# VA-Meter_Measure.net
KiCad netlist of a schematic drawn in EAGLE
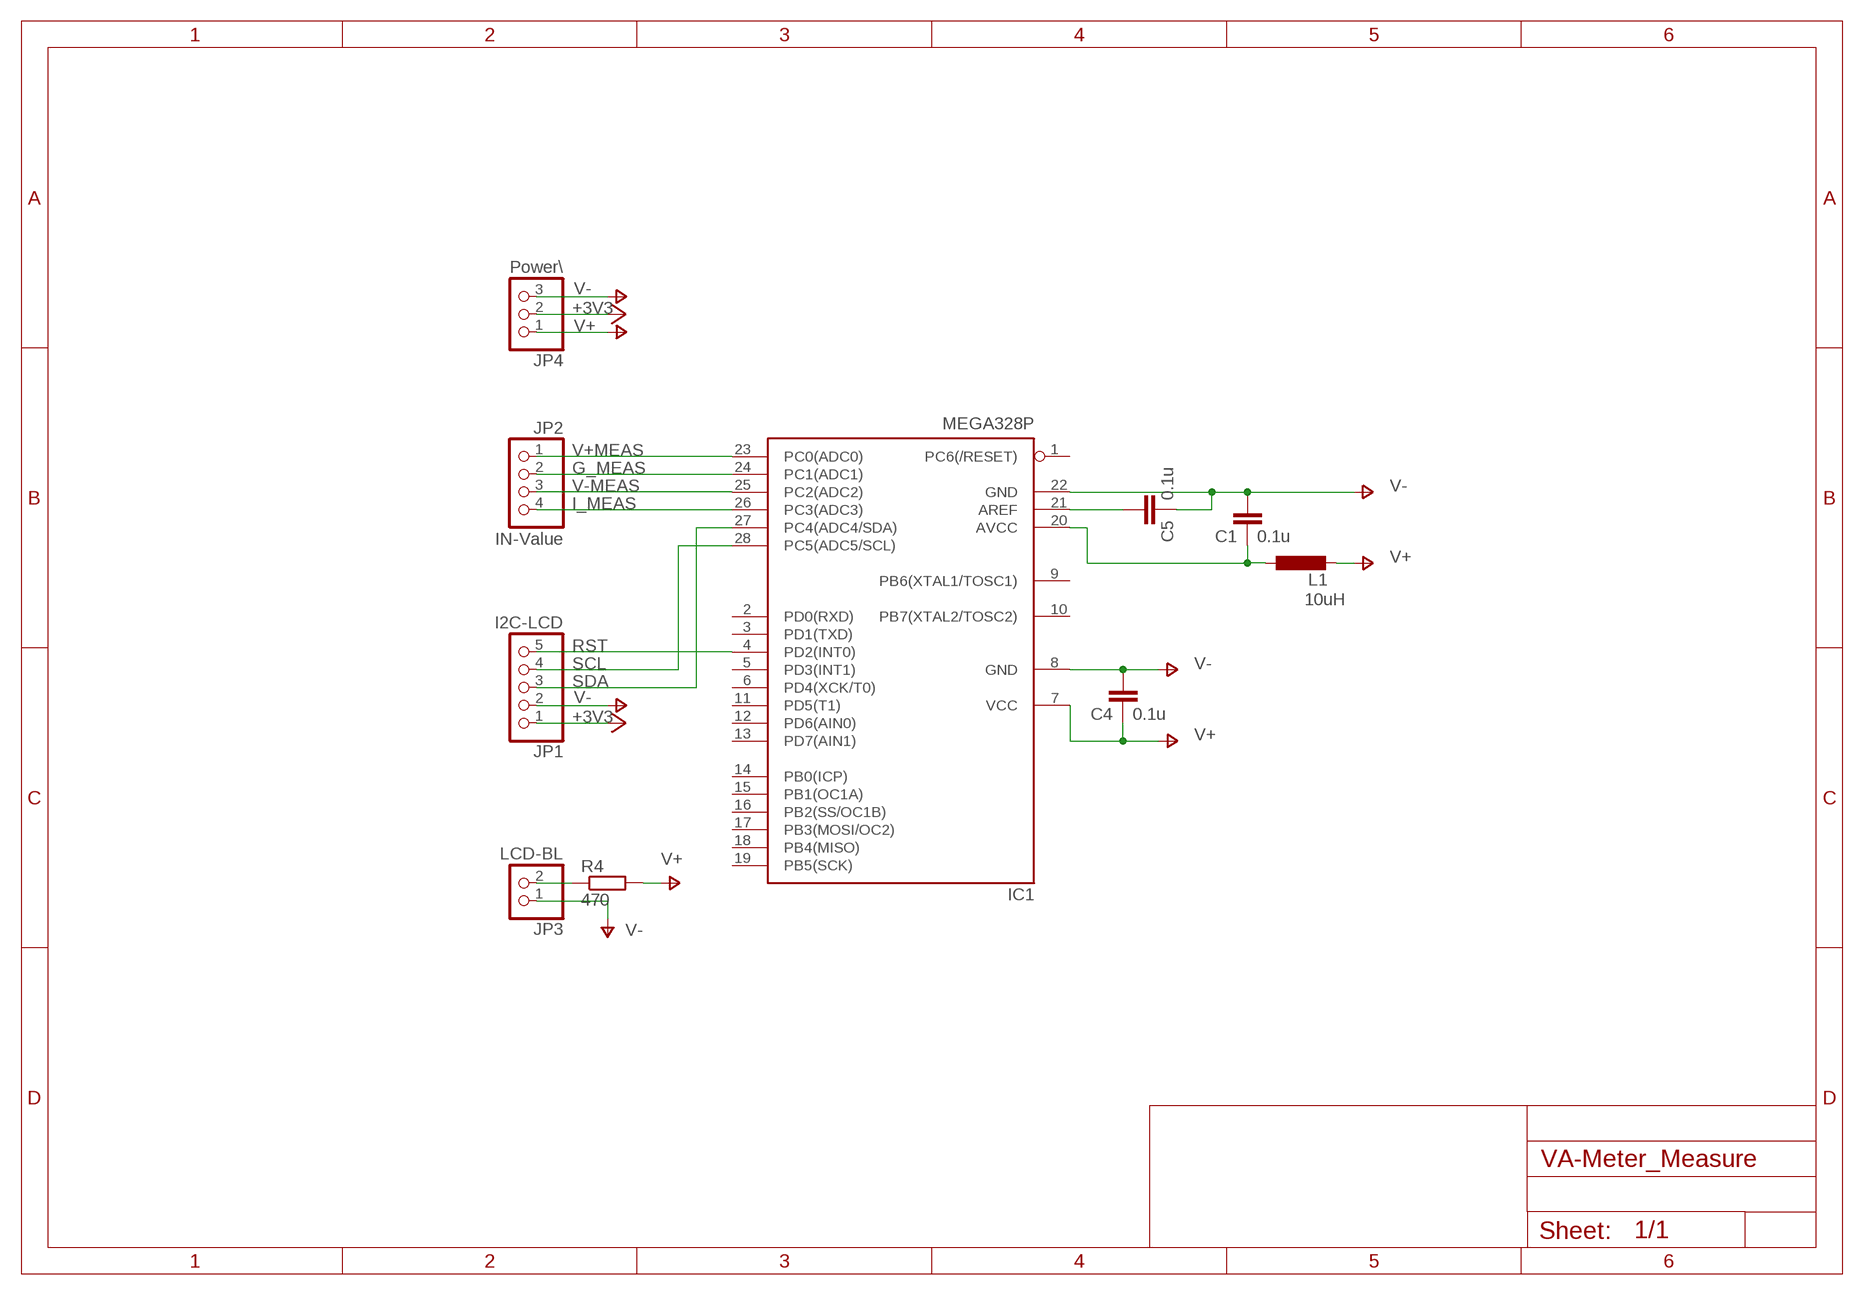
[diagram p0: schematic, sheet 1]

(export (version "E")
  (design (tool "Eeschema 10.0.6"))
  (components
    (comp (ref "C1")
      (value "0.1u")
      (footprint "eagle-import:C050-024X044")
      (libsource (lib "eagle-import") (part "C-EU050-024X044"))
    )
    (comp (ref "C4")
      (value "0.1u")
      (footprint "eagle-import:C050-024X044")
      (libsource (lib "eagle-import") (part "C-EU050-024X044"))
    )
    (comp (ref "C5")
      (value "0.1u")
      (footprint "eagle-import:C050-024X044")
      (libsource (lib "eagle-import") (part "C-EU050-024X044"))
    )
    (comp (ref "IC1")
      (value "MEGA328P")
      (footprint "eagle-import:MEGA328P")
      (libsource (lib "eagle-import") (part "MEGA328P"))
    )
    (comp (ref "JP1")
      (value "I2C-LCD")
      (footprint "eagle-import:1X05")
      (libsource (lib "eagle-import") (part "PINHD-1X5"))
    )
    (comp (ref "JP2")
      (value "IN-Value")
      (footprint "eagle-import:1X04")
      (libsource (lib "eagle-import") (part "PINHD-1X4"))
    )
    (comp (ref "JP3")
      (value "LCD-BL")
      (footprint "eagle-import:1X02")
      (libsource (lib "eagle-import") (part "PINHD-1X2"))
    )
    (comp (ref "JP4")
      (value "Power\\")
      (footprint "eagle-import:1X03")
      (libsource (lib "eagle-import") (part "PINHD-1X3"))
    )
    (comp (ref "L1")
      (value "10uH")
      (footprint "eagle-import:6000-XXXX-RC")
      (libsource (lib "eagle-import") (part "L-EU6000-XXX-RC"))
    )
    (comp (ref "R4")
      (value "470")
      (footprint "eagle-import:0207_7")
      (libsource (lib "eagle-import") (part "R-EU_0207/7"))
    )
  )
  (nets
    (net (code "1") (name "+3V3") (class "Default")
      (node (ref "JP1") (pin "1") (pinfunction "1_1") (pintype "passive"))
      (node (ref "JP4") (pin "2") (pinfunction "2_2") (pintype "passive"))
    )
    (net (code "2") (name "/G_MEAS") (class "Default")
      (node (ref "IC1") (pin "24") (pinfunction "PC1(ADC1)_24") (pintype "bidirectional"))
      (node (ref "JP2") (pin "2") (pinfunction "2_2") (pintype "passive"))
    )
    (net (code "3") (name "/I_MEAS") (class "Default")
      (node (ref "IC1") (pin "26") (pinfunction "PC3(ADC3)_26") (pintype "bidirectional"))
      (node (ref "JP2") (pin "4") (pinfunction "4_4") (pintype "passive"))
    )
    (net (code "4") (name "/RST") (class "Default")
      (node (ref "IC1") (pin "4") (pinfunction "PD2(INT0)_4") (pintype "bidirectional"))
      (node (ref "JP1") (pin "5") (pinfunction "5_5") (pintype "passive"))
    )
    (net (code "5") (name "/SCL") (class "Default")
      (node (ref "IC1") (pin "28") (pinfunction "PC5(ADC5/SCL)_28") (pintype "bidirectional"))
      (node (ref "JP1") (pin "4") (pinfunction "4_4") (pintype "passive"))
    )
    (net (code "6") (name "/SDA") (class "Default")
      (node (ref "IC1") (pin "27") (pinfunction "PC4(ADC4/SDA)_27") (pintype "bidirectional"))
      (node (ref "JP1") (pin "3") (pinfunction "3_3") (pintype "passive"))
    )
    (net (code "7") (name "/V+MEAS") (class "Default")
      (node (ref "IC1") (pin "23") (pinfunction "PC0(ADC0)_23") (pintype "bidirectional"))
      (node (ref "JP2") (pin "1") (pinfunction "1_1") (pintype "passive"))
    )
    (net (code "8") (name "/V-MEAS") (class "Default")
      (node (ref "IC1") (pin "25") (pinfunction "PC2(ADC2)_25") (pintype "bidirectional"))
      (node (ref "JP2") (pin "3") (pinfunction "3_3") (pintype "passive"))
    )
    (net (code "9") (name "Net-(IC1-AREF)") (class "Default")
      (node (ref "C5") (pin "2") (pinfunction "2_2") (pintype "passive"))
      (node (ref "IC1") (pin "21") (pinfunction "AREF_21") (pintype "passive"))
    )
    (net (code "10") (name "Net-(IC1-AVCC)") (class "Default")
      (node (ref "C1") (pin "1") (pinfunction "1_1") (pintype "passive"))
      (node (ref "IC1") (pin "20") (pinfunction "AVCC_20") (pintype "power_in"))
      (node (ref "L1") (pin "1") (pinfunction "1_1") (pintype "passive"))
    )
    (net (code "11") (name "Net-(JP3-Pad2)") (class "Default")
      (node (ref "JP3") (pin "2") (pinfunction "2_2") (pintype "passive"))
      (node (ref "R4") (pin "1") (pinfunction "1_1") (pintype "passive"))
    )
    (net (code "12") (name "V+") (class "Default")
      (node (ref "C4") (pin "1") (pinfunction "1_1") (pintype "passive"))
      (node (ref "IC1") (pin "7") (pinfunction "VCC_7") (pintype "power_in"))
      (node (ref "JP4") (pin "1") (pinfunction "1_1") (pintype "passive"))
      (node (ref "L1") (pin "2") (pinfunction "2_2") (pintype "passive"))
      (node (ref "R4") (pin "2") (pinfunction "2_2") (pintype "passive"))
    )
    (net (code "13") (name "V-") (class "Default")
      (node (ref "C1") (pin "2") (pinfunction "2_2") (pintype "passive"))
      (node (ref "C4") (pin "2") (pinfunction "2_2") (pintype "passive"))
      (node (ref "C5") (pin "1") (pinfunction "1_1") (pintype "passive"))
      (node (ref "IC1") (pin "22") (pinfunction "GND_22") (pintype "power_in"))
      (node (ref "IC1") (pin "8") (pinfunction "GND_8") (pintype "power_in"))
      (node (ref "JP1") (pin "2") (pinfunction "2_2") (pintype "passive"))
      (node (ref "JP3") (pin "1") (pinfunction "1_1") (pintype "passive"))
      (node (ref "JP4") (pin "3") (pinfunction "3_3") (pintype "passive"))
    )
    (net (code "14") (name "unconnected-(IC1-PB0(ICP)-Pad14)") (class "Default")
      (node (ref "IC1") (pin "14") (pinfunction "PB0(ICP)_14") (pintype "bidirectional"))
    )
    (net (code "15") (name "unconnected-(IC1-PB1(OC1A)-Pad15)") (class "Default")
      (node (ref "IC1") (pin "15") (pinfunction "PB1(OC1A)_15") (pintype "bidirectional"))
    )
    (net (code "16") (name "unconnected-(IC1-PB2(SS{slash}OC1B)-Pad16)") (class "Default")
      (node (ref "IC1") (pin "16") (pinfunction "PB2(SS/OC1B)_16") (pintype "bidirectional"))
    )
    (net (code "17") (name "unconnected-(IC1-PB3(MOSI{slash}OC2)-Pad17)") (class "Default")
      (node (ref "IC1") (pin "17") (pinfunction "PB3(MOSI/OC2)_17") (pintype "bidirectional"))
    )
    (net (code "18") (name "unconnected-(IC1-PB4(MISO)-Pad18)") (class "Default")
      (node (ref "IC1") (pin "18") (pinfunction "PB4(MISO)_18") (pintype "bidirectional"))
    )
    (net (code "19") (name "unconnected-(IC1-PB5(SCK)-Pad19)") (class "Default")
      (node (ref "IC1") (pin "19") (pinfunction "PB5(SCK)_19") (pintype "bidirectional"))
    )
    (net (code "20") (name "unconnected-(IC1-PB6(XTAL1{slash}TOSC1)-Pad9)") (class "Default")
      (node (ref "IC1") (pin "9") (pinfunction "PB6(XTAL1/TOSC1)_9") (pintype "bidirectional"))
    )
    (net (code "21") (name "unconnected-(IC1-PB7(XTAL2{slash}TOSC2)-Pad10)") (class "Default")
      (node (ref "IC1") (pin "10") (pinfunction "PB7(XTAL2/TOSC2)_10") (pintype "bidirectional"))
    )
    (net (code "22") (name "unconnected-(IC1-PC6({slash}RESET)-Pad1)") (class "Default")
      (node (ref "IC1") (pin "1") (pinfunction "PC6(/RESET)_1") (pintype "bidirectional"))
    )
    (net (code "23") (name "unconnected-(IC1-PD0(RXD)-Pad2)") (class "Default")
      (node (ref "IC1") (pin "2") (pinfunction "PD0(RXD)_2") (pintype "bidirectional"))
    )
    (net (code "24") (name "unconnected-(IC1-PD1(TXD)-Pad3)") (class "Default")
      (node (ref "IC1") (pin "3") (pinfunction "PD1(TXD)_3") (pintype "bidirectional"))
    )
    (net (code "25") (name "unconnected-(IC1-PD3(INT1)-Pad5)") (class "Default")
      (node (ref "IC1") (pin "5") (pinfunction "PD3(INT1)_5") (pintype "bidirectional"))
    )
    (net (code "26") (name "unconnected-(IC1-PD4(XCK{slash}T0)-Pad6)") (class "Default")
      (node (ref "IC1") (pin "6") (pinfunction "PD4(XCK/T0)_6") (pintype "bidirectional"))
    )
    (net (code "27") (name "unconnected-(IC1-PD5(T1)-Pad11)") (class "Default")
      (node (ref "IC1") (pin "11") (pinfunction "PD5(T1)_11") (pintype "bidirectional"))
    )
    (net (code "28") (name "unconnected-(IC1-PD6(AIN0)-Pad12)") (class "Default")
      (node (ref "IC1") (pin "12") (pinfunction "PD6(AIN0)_12") (pintype "bidirectional"))
    )
    (net (code "29") (name "unconnected-(IC1-PD7(AIN1)-Pad13)") (class "Default")
      (node (ref "IC1") (pin "13") (pinfunction "PD7(AIN1)_13") (pintype "bidirectional"))
    )
  )
)
